# Schematic_lampe.net
KiCad netlist of a schematic drawn in Altium Designer
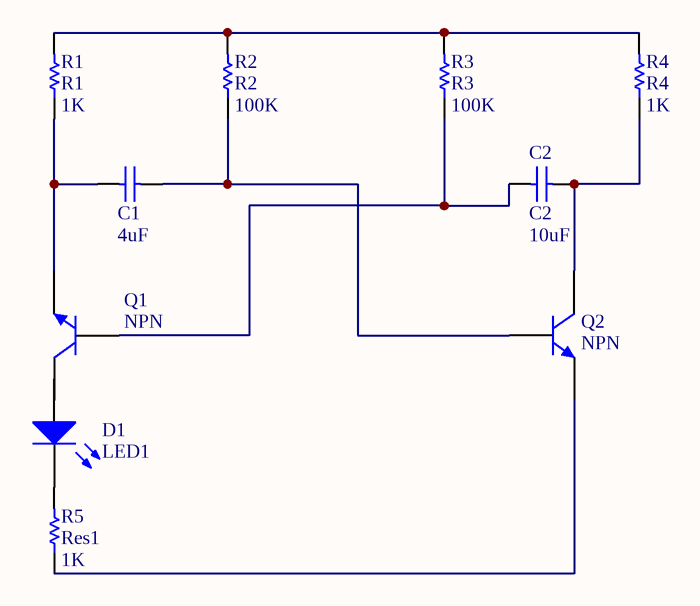
[diagram p0: Schematic_lampe.SchDoc]

(export (version "E")
  (design (tool "Eeschema 10.0.6"))
  (components
    (comp (ref "C1")
      (value "C1")
      (footprint "RAD-0.3")
      (description "Capacitor")
      (fields (field (name "ALTIUM_VALUE") "4uF") (field (name "PUBLISHER") "Altium Limited"))
      (libsource (lib "Miscellaneous Devices") (part "Cap"))
    )
    (comp (ref "C2")
      (value "C2")
      (footprint "RAD-0.3")
      (description "Capacitor")
      (fields (field (name "ALTIUM_VALUE") "10uF") (field (name "PUBLISHER") "Altium Limited"))
      (libsource (lib "Miscellaneous Devices") (part "Cap"))
    )
    (comp (ref "D1")
      (value "LED1")
      (footprint "LED-1")
      (description "Typical RED GaAs LED")
      (fields (field (name "PUBLISHER") "Altium Limited"))
      (libsource (lib "Miscellaneous Devices") (part "LED1"))
    )
    (comp (ref "Q1")
      (value "NPN")
      (footprint "TO-226-AA")
      (description "NPN Bipolar Transistor")
      (fields (field (name "PUBLISHER") "Altium Limited"))
      (libsource (lib "Miscellaneous Devices") (part "NPN"))
    )
    (comp (ref "Q2")
      (value "NPN")
      (footprint "TO-226-AA")
      (description "NPN Bipolar Transistor")
      (fields (field (name "PUBLISHER") "Altium Limited"))
      (libsource (lib "Miscellaneous Devices") (part "NPN"))
    )
    (comp (ref "R1")
      (value "R1")
      (footprint "AXIAL-0.3")
      (description "Resistor")
      (fields (field (name "ALTIUM_VALUE") "1K") (field (name "PUBLISHER") "Altium Limited"))
      (libsource (lib "Miscellaneous Devices") (part "Res1"))
    )
    (comp (ref "R2")
      (value "R2")
      (footprint "AXIAL-0.3")
      (description "Resistor")
      (fields (field (name "ALTIUM_VALUE") "100K") (field (name "PUBLISHER") "Altium Limited"))
      (libsource (lib "Miscellaneous Devices") (part "Res1"))
    )
    (comp (ref "R3")
      (value "R3")
      (footprint "Resistor 1206")
      (description "Resistor")
      (fields (field (name "ALTIUM_VALUE") "100K") (field (name "PUBLISHER") "Altium Limited"))
      (libsource (lib "Miscellaneous Devices") (part "Res1"))
    )
    (comp (ref "R4")
      (value "R4")
      (footprint "AXIAL-0.3")
      (description "Resistor")
      (fields (field (name "ALTIUM_VALUE") "1K") (field (name "PUBLISHER") "Altium Limited"))
      (libsource (lib "Miscellaneous Devices") (part "Res1"))
    )
    (comp (ref "R5")
      (value "Res1")
      (footprint "AXIAL-0.3")
      (description "Resistor")
      (fields (field (name "ALTIUM_VALUE") "1K") (field (name "PUBLISHER") "Altium Limited"))
      (libsource (lib "Miscellaneous Devices") (part "Res1"))
    )
  )
  (nets
    (net (code "1") (name "Net-(D1-K)") (class "Default")
      (node (ref "D1") (pin "2") (pinfunction "K_2") (pintype "passive"))
      (node (ref "R5") (pin "2") (pinfunction "2_2") (pintype "passive"))
    )
    (net (code "2") (name "Net-(Q1-B)") (class "Default")
      (node (ref "C2") (pin "1") (pinfunction "1_1") (pintype "passive"))
      (node (ref "Q1") (pin "2") (pinfunction "B_2") (pintype "passive"))
      (node (ref "R3") (pin "1") (pinfunction "1_1") (pintype "passive"))
    )
    (net (code "3") (name "Net-(Q1-E)") (class "Default")
      (node (ref "C1") (pin "1") (pinfunction "1_1") (pintype "passive"))
      (node (ref "Q1") (pin "3") (pinfunction "E_3") (pintype "passive"))
      (node (ref "R1") (pin "1") (pinfunction "1_1") (pintype "passive"))
    )
    (net (code "4") (name "Net-(Q2-B)") (class "Default")
      (node (ref "C1") (pin "2") (pinfunction "2_2") (pintype "passive"))
      (node (ref "Q2") (pin "2") (pinfunction "B_2") (pintype "passive"))
      (node (ref "R2") (pin "1") (pinfunction "1_1") (pintype "passive"))
    )
    (net (code "5") (name "Net-(Q2-C)") (class "Default")
      (node (ref "C2") (pin "2") (pinfunction "2_2") (pintype "passive"))
      (node (ref "Q2") (pin "1") (pinfunction "C_1") (pintype "passive"))
      (node (ref "R4") (pin "1") (pinfunction "1_1") (pintype "passive"))
    )
    (net (code "6") (name "Net-(Q2-E)") (class "Default")
      (node (ref "Q2") (pin "3") (pinfunction "E_3") (pintype "passive"))
      (node (ref "R5") (pin "1") (pinfunction "1_1") (pintype "passive"))
    )
    (net (code "7") (name "Net-(R1-Pad2)") (class "Default")
      (node (ref "R1") (pin "2") (pinfunction "2_2") (pintype "passive"))
      (node (ref "R2") (pin "2") (pinfunction "2_2") (pintype "passive"))
      (node (ref "R3") (pin "2") (pinfunction "2_2") (pintype "passive"))
      (node (ref "R4") (pin "2") (pinfunction "2_2") (pintype "passive"))
    )
    (net (code "8") (name "unconnected-(D1-A-Pad1)") (class "Default")
      (node (ref "D1") (pin "1") (pinfunction "A_1") (pintype "passive"))
    )
    (net (code "9") (name "unconnected-(Q1-C-Pad1)") (class "Default")
      (node (ref "Q1") (pin "1") (pinfunction "C_1") (pintype "passive"))
    )
  )
)
